# linearSensor.net
KiCad netlist of a schematic drawn in EAGLE
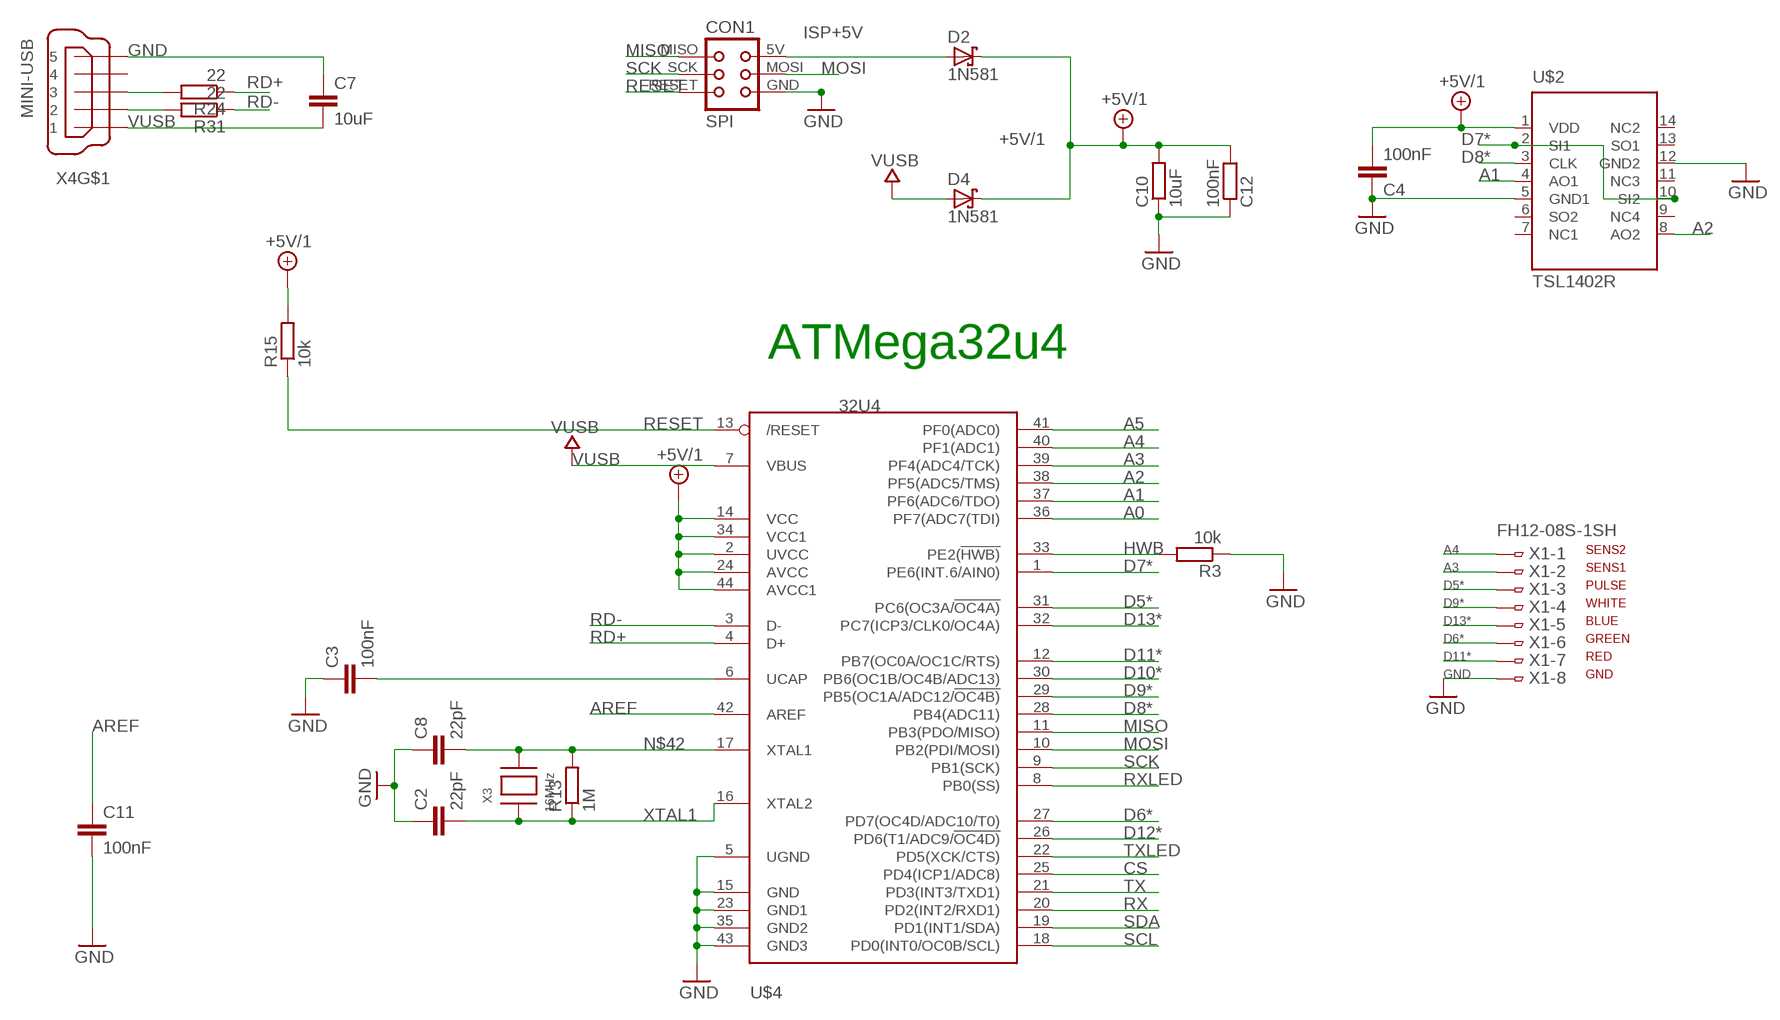
[diagram p0: schematic, sheet 1]

(export (version "E")
  (design (tool "Eeschema 10.0.6"))
  (components
    (comp (ref "C2")
      (value "22pF")
      (footprint "eagle-import:C0805K")
      (libsource (lib "eagle-import") (part "C-EUC0805K"))
    )
    (comp (ref "C3")
      (value "100nF")
      (footprint "eagle-import:C0805K")
      (libsource (lib "eagle-import") (part "C-EUC0805K"))
    )
    (comp (ref "C4")
      (value "100nF")
      (footprint "eagle-import:C0805")
      (libsource (lib "eagle-import") (part "C-EUC0805"))
    )
    (comp (ref "C7")
      (value "10uF")
      (footprint "eagle-import:C0805")
      (libsource (lib "eagle-import") (part "C-EUC0805"))
    )
    (comp (ref "C8")
      (value "22pF")
      (footprint "eagle-import:C0805K")
      (libsource (lib "eagle-import") (part "C-EUC0805K"))
    )
    (comp (ref "C10")
      (value "10uF")
      (footprint "eagle-import:M0805")
      (libsource (lib "eagle-import") (part "R-EU_M0805"))
    )
    (comp (ref "C11")
      (value "100nF")
      (footprint "eagle-import:C0805K")
      (libsource (lib "eagle-import") (part "C-EUC0805K"))
    )
    (comp (ref "C12")
      (value "100nF")
      (footprint "eagle-import:M0805")
      (libsource (lib "eagle-import") (part "R-EU_M0805"))
    )
    (comp (ref "CON1")
      (value "SPI")
      (footprint "eagle-import:TC2030-MCP-NL")
      (libsource (lib "eagle-import") (part "TINYISPT"))
    )
    (comp (ref "D2")
      (value "1N581")
      (footprint "eagle-import:LED-1206")
      (libsource (lib "eagle-import") (part "1N581D1206"))
    )
    (comp (ref "D4")
      (value "1N581")
      (footprint "eagle-import:LED-1206")
      (libsource (lib "eagle-import") (part "1N581D1206"))
    )
    (comp (ref "R3")
      (value "10k")
      (footprint "eagle-import:M0805")
      (libsource (lib "eagle-import") (part "resistor_R-EU_M0805"))
    )
    (comp (ref "R13")
      (value "1M")
      (footprint "eagle-import:M0805")
      (libsource (lib "eagle-import") (part "R-EU_M0805"))
    )
    (comp (ref "R15")
      (value "10k")
      (footprint "eagle-import:M0805")
      (libsource (lib "eagle-import") (part "resistor_R-EU_M0805"))
    )
    (comp (ref "R24")
      (value "22")
      (footprint "eagle-import:M0805")
      (libsource (lib "eagle-import") (part "R-EU_M0805"))
    )
    (comp (ref "R31")
      (value "22")
      (footprint "eagle-import:M0805")
      (libsource (lib "eagle-import") (part "R-EU_M0805"))
    )
    (comp (ref "U$2")
      (value "TSL1402R")
      (footprint "eagle-import:DIL14")
      (libsource (lib "eagle-import") (part "TSL1402R"))
    )
    (comp (ref "U$4")
      (value "32U4")
      (footprint "eagle-import:TQFP44")
      (libsource (lib "eagle-import") (part "ATMEGA32U4-AU"))
    )
    (comp (ref "X1")
      (value "FH12-08S-1SH")
      (footprint "eagle-import:FH12-08S-1SH")
      (libsource (lib "eagle-import") (part "FH12-08S-1SH"))
    )
    (comp (ref "X3")
      (value "16MHz")
      (footprint "eagle-import:NX6035")
      (libsource (lib "eagle-import") (part "XTALNX6035"))
    )
    (comp (ref "X4")
      (value "MINI-USB")
      (footprint "eagle-import:32005-201")
      (libsource (lib "eagle-import") (part "MINI-USB-SCHIELD-32005-201"))
    )
  )
  (nets
    (net (code "1") (name "+5V{slash}1") (class "Default")
      (node (ref "C10") (pin "2") (pinfunction "2_2") (pintype "passive"))
      (node (ref "C12") (pin "2") (pinfunction "2_2") (pintype "passive"))
      (node (ref "C4") (pin "2") (pinfunction "2_2") (pintype "passive"))
      (node (ref "D2") (pin "C") (pinfunction "C_C") (pintype "passive"))
      (node (ref "D4") (pin "C") (pinfunction "C_C") (pintype "passive"))
      (node (ref "R15") (pin "2") (pinfunction "2_2") (pintype "passive"))
      (node (ref "U$2") (pin "1") (pinfunction "VDD_1") (pintype "power_in"))
      (node (ref "U$4") (pin "14") (pinfunction "VCC_14") (pintype "bidirectional"))
      (node (ref "U$4") (pin "2") (pinfunction "UVCC_2") (pintype "bidirectional"))
      (node (ref "U$4") (pin "24") (pinfunction "AVCC_24") (pintype "bidirectional"))
      (node (ref "U$4") (pin "34") (pinfunction "VCC1_34") (pintype "bidirectional"))
      (node (ref "U$4") (pin "44") (pinfunction "AVCC1_44") (pintype "bidirectional"))
    )
    (net (code "2") (name "/A0") (class "Default")
      (node (ref "U$4") (pin "36") (pinfunction "PF7(ADC7(TDI)_36") (pintype "bidirectional"))
    )
    (net (code "3") (name "/A1") (class "Default")
      (node (ref "U$2") (pin "4") (pinfunction "AO1_4") (pintype "output"))
      (node (ref "U$4") (pin "37") (pinfunction "PF6(ADC6/TDO)_37") (pintype "bidirectional"))
    )
    (net (code "4") (name "/A2") (class "Default")
      (node (ref "U$2") (pin "8") (pinfunction "AO2_8") (pintype "output"))
      (node (ref "U$4") (pin "38") (pinfunction "PF5(ADC5/TMS)_38") (pintype "bidirectional"))
    )
    (net (code "5") (name "/A3") (class "Default")
      (node (ref "U$4") (pin "39") (pinfunction "PF4(ADC4/TCK)_39") (pintype "bidirectional"))
      (node (ref "X1") (pin "2") (pinfunction "1_2") (pintype "passive"))
    )
    (net (code "6") (name "/A4") (class "Default")
      (node (ref "U$4") (pin "40") (pinfunction "PF1(ADC1)_40") (pintype "bidirectional"))
      (node (ref "X1") (pin "1") (pinfunction "1_1") (pintype "passive"))
    )
    (net (code "7") (name "/A5") (class "Default")
      (node (ref "U$4") (pin "41") (pinfunction "PF0(ADC0)_41") (pintype "bidirectional"))
    )
    (net (code "8") (name "/AREF") (class "Default")
      (node (ref "C11") (pin "1") (pinfunction "1_1") (pintype "passive"))
      (node (ref "U$4") (pin "42") (pinfunction "AREF_42") (pintype "bidirectional"))
    )
    (net (code "9") (name "/CS") (class "Default")
      (node (ref "U$4") (pin "25") (pinfunction "PD4(ICP1/ADC8)_25") (pintype "bidirectional"))
    )
    (net (code "10") (name "/D5*") (class "Default")
      (node (ref "U$4") (pin "31") (pinfunction "PC6(OC3A/~{OC4A})_31") (pintype "bidirectional"))
      (node (ref "X1") (pin "3") (pinfunction "1_3") (pintype "passive"))
    )
    (net (code "11") (name "/D6*") (class "Default")
      (node (ref "U$4") (pin "27") (pinfunction "PD7(OC4D/ADC10/T0)_27") (pintype "bidirectional"))
      (node (ref "X1") (pin "6") (pinfunction "1_6") (pintype "passive"))
    )
    (net (code "12") (name "/D7*") (class "Default")
      (node (ref "U$2") (pin "10") (pinfunction "SI2_10") (pintype "input"))
      (node (ref "U$2") (pin "2") (pinfunction "SI1_2") (pintype "input"))
      (node (ref "U$4") (pin "1") (pinfunction "PE6(INT.6/AIN0)_1") (pintype "bidirectional"))
    )
    (net (code "13") (name "/D8*") (class "Default")
      (node (ref "U$2") (pin "3") (pinfunction "CLK_3") (pintype "input"))
      (node (ref "U$4") (pin "28") (pinfunction "PB4(ADC11)_28") (pintype "bidirectional"))
    )
    (net (code "14") (name "/D9*") (class "Default")
      (node (ref "U$4") (pin "29") (pinfunction "PB5(OC1A/ADC12/~{OC4B})_29") (pintype "bidirectional"))
      (node (ref "X1") (pin "4") (pinfunction "1_4") (pintype "passive"))
    )
    (net (code "15") (name "/D10*") (class "Default")
      (node (ref "U$4") (pin "30") (pinfunction "PB6(OC1B/OC4B/ADC13)_30") (pintype "bidirectional"))
    )
    (net (code "16") (name "/D11*") (class "Default")
      (node (ref "U$4") (pin "12") (pinfunction "PB7(OC0A/OC1C/RTS)_12") (pintype "bidirectional"))
      (node (ref "X1") (pin "7") (pinfunction "1_7") (pintype "passive"))
    )
    (net (code "17") (name "/D12*") (class "Default")
      (node (ref "U$4") (pin "26") (pinfunction "PD6(T1/ADC9/~{OC4D})_26") (pintype "bidirectional"))
    )
    (net (code "18") (name "/D13*") (class "Default")
      (node (ref "U$4") (pin "32") (pinfunction "PC7(ICP3/CLK0/OC4A)_32") (pintype "bidirectional"))
      (node (ref "X1") (pin "5") (pinfunction "1_5") (pintype "passive"))
    )
    (net (code "19") (name "/HWB") (class "Default")
      (node (ref "R3") (pin "2") (pinfunction "2_2") (pintype "passive"))
      (node (ref "U$4") (pin "33") (pinfunction "PE2(~{HWB})_33") (pintype "bidirectional"))
    )
    (net (code "20") (name "/ISP+5V") (class "Default")
      (node (ref "CON1") (pin "5V") (pinfunction "VCC_5V") (pintype "passive"))
      (node (ref "D2") (pin "A") (pinfunction "A_A") (pintype "passive"))
    )
    (net (code "21") (name "/MISO") (class "Default")
      (node (ref "CON1") (pin "MISO") (pinfunction "MISO_MISO") (pintype "passive"))
      (node (ref "U$4") (pin "11") (pinfunction "PB3(PDO/MISO)_11") (pintype "bidirectional"))
    )
    (net (code "22") (name "/MOSI") (class "Default")
      (node (ref "CON1") (pin "MOSI") (pinfunction "MOSI_MOSI") (pintype "passive"))
      (node (ref "U$4") (pin "10") (pinfunction "PB2(PDI/MOSI)_10") (pintype "bidirectional"))
    )
    (net (code "23") (name "/N$42") (class "Default")
      (node (ref "C8") (pin "2") (pinfunction "2_2") (pintype "passive"))
      (node (ref "R13") (pin "2") (pinfunction "2_2") (pintype "passive"))
      (node (ref "U$4") (pin "17") (pinfunction "XTAL1_17") (pintype "bidirectional"))
      (node (ref "X3") (pin "P$2") (pinfunction "P$2_P$2") (pintype "bidirectional"))
    )
    (net (code "24") (name "/RD+") (class "Default")
      (node (ref "R24") (pin "1") (pinfunction "1_1") (pintype "passive"))
      (node (ref "U$4") (pin "4") (pinfunction "D+_4") (pintype "bidirectional"))
    )
    (net (code "25") (name "/RD-") (class "Default")
      (node (ref "R31") (pin "1") (pinfunction "1_1") (pintype "passive"))
      (node (ref "U$4") (pin "3") (pinfunction "D-_3") (pintype "bidirectional"))
    )
    (net (code "26") (name "/RESET") (class "Default")
      (node (ref "CON1") (pin "RESET") (pinfunction "RESET_RESET") (pintype "passive"))
      (node (ref "R15") (pin "1") (pinfunction "1_1") (pintype "passive"))
      (node (ref "U$4") (pin "13") (pinfunction "/RESET_13") (pintype "bidirectional"))
    )
    (net (code "27") (name "/RX") (class "Default")
      (node (ref "U$4") (pin "20") (pinfunction "PD2(INT2/RXD1)_20") (pintype "bidirectional"))
    )
    (net (code "28") (name "/RXLED") (class "Default")
      (node (ref "U$4") (pin "8") (pinfunction "PB0(SS)_8") (pintype "bidirectional"))
    )
    (net (code "29") (name "/SCK") (class "Default")
      (node (ref "CON1") (pin "SCK") (pinfunction "SCK_SCK") (pintype "passive"))
      (node (ref "U$4") (pin "9") (pinfunction "PB1(SCK)_9") (pintype "bidirectional"))
    )
    (net (code "30") (name "/SCL") (class "Default")
      (node (ref "U$4") (pin "18") (pinfunction "PD0(INT0/OC0B/SCL)_18") (pintype "bidirectional"))
    )
    (net (code "31") (name "/SDA") (class "Default")
      (node (ref "U$4") (pin "19") (pinfunction "PD1(INT1/SDA)_19") (pintype "bidirectional"))
    )
    (net (code "32") (name "/TX") (class "Default")
      (node (ref "U$4") (pin "21") (pinfunction "PD3(INT3/TXD1)_21") (pintype "bidirectional"))
    )
    (net (code "33") (name "/TXLED") (class "Default")
      (node (ref "U$4") (pin "22") (pinfunction "PD5(XCK/CTS)_22") (pintype "bidirectional"))
    )
    (net (code "34") (name "/XTAL1") (class "Default")
      (node (ref "C2") (pin "2") (pinfunction "2_2") (pintype "passive"))
      (node (ref "R13") (pin "1") (pinfunction "1_1") (pintype "passive"))
      (node (ref "U$4") (pin "16") (pinfunction "XTAL2_16") (pintype "bidirectional"))
      (node (ref "X3") (pin "P$1") (pinfunction "P$1_P$1") (pintype "bidirectional"))
    )
    (net (code "35") (name "GND") (class "Default")
      (node (ref "C10") (pin "1") (pinfunction "1_1") (pintype "passive"))
      (node (ref "C11") (pin "2") (pinfunction "2_2") (pintype "passive"))
      (node (ref "C12") (pin "1") (pinfunction "1_1") (pintype "passive"))
      (node (ref "C2") (pin "1") (pinfunction "1_1") (pintype "passive"))
      (node (ref "C3") (pin "1") (pinfunction "1_1") (pintype "passive"))
      (node (ref "C4") (pin "1") (pinfunction "1_1") (pintype "passive"))
      (node (ref "C7") (pin "1") (pinfunction "1_1") (pintype "passive"))
      (node (ref "C8") (pin "1") (pinfunction "1_1") (pintype "passive"))
      (node (ref "CON1") (pin "GND") (pinfunction "GND_GND") (pintype "passive"))
      (node (ref "R3") (pin "1") (pinfunction "1_1") (pintype "passive"))
      (node (ref "U$2") (pin "12") (pinfunction "GND2_12") (pintype "power_in"))
      (node (ref "U$2") (pin "5") (pinfunction "GND1_5") (pintype "power_in"))
      (node (ref "U$4") (pin "15") (pinfunction "GND_15") (pintype "bidirectional"))
      (node (ref "U$4") (pin "23") (pinfunction "GND1_23") (pintype "bidirectional"))
      (node (ref "U$4") (pin "35") (pinfunction "GND2_35") (pintype "bidirectional"))
      (node (ref "U$4") (pin "43") (pinfunction "GND3_43") (pintype "bidirectional"))
      (node (ref "U$4") (pin "5") (pinfunction "UGND_5") (pintype "bidirectional"))
      (node (ref "X1") (pin "8") (pinfunction "1_8") (pintype "passive"))
      (node (ref "X4") (pin "5") (pinfunction "5_5") (pintype "passive"))
    )
    (net (code "36") (name "Net-(R24-Pad2)") (class "Default")
      (node (ref "R24") (pin "2") (pinfunction "2_2") (pintype "passive"))
      (node (ref "X4") (pin "3") (pinfunction "3_3") (pintype "passive"))
    )
    (net (code "37") (name "Net-(R31-Pad2)") (class "Default")
      (node (ref "R31") (pin "2") (pinfunction "2_2") (pintype "passive"))
      (node (ref "X4") (pin "2") (pinfunction "2_2") (pintype "passive"))
    )
    (net (code "38") (name "Net-(U$4-UCAP)") (class "Default")
      (node (ref "C3") (pin "2") (pinfunction "2_2") (pintype "passive"))
      (node (ref "U$4") (pin "6") (pinfunction "UCAP_6") (pintype "bidirectional"))
    )
    (net (code "39") (name "VUSB") (class "Default")
      (node (ref "C7") (pin "2") (pinfunction "2_2") (pintype "passive"))
      (node (ref "D4") (pin "A") (pinfunction "A_A") (pintype "passive"))
      (node (ref "U$4") (pin "7") (pinfunction "VBUS_7") (pintype "bidirectional"))
      (node (ref "X4") (pin "1") (pinfunction "1_1") (pintype "passive"))
    )
    (net (code "40") (name "unconnected-(U$2-NC1-Pad7)") (class "Default")
      (node (ref "U$2") (pin "7") (pinfunction "NC1_7") (pintype "no_connect"))
    )
    (net (code "41") (name "unconnected-(U$2-NC2-Pad14)") (class "Default")
      (node (ref "U$2") (pin "14") (pinfunction "NC2_14") (pintype "no_connect"))
    )
    (net (code "42") (name "unconnected-(U$2-NC3-Pad11)") (class "Default")
      (node (ref "U$2") (pin "11") (pinfunction "NC3_11") (pintype "no_connect"))
    )
    (net (code "43") (name "unconnected-(U$2-NC4-Pad9)") (class "Default")
      (node (ref "U$2") (pin "9") (pinfunction "NC4_9") (pintype "no_connect"))
    )
    (net (code "44") (name "unconnected-(U$2-SO1-Pad13)") (class "Default")
      (node (ref "U$2") (pin "13") (pinfunction "SO1_13") (pintype "output"))
    )
    (net (code "45") (name "unconnected-(U$2-SO2-Pad6)") (class "Default")
      (node (ref "U$2") (pin "6") (pinfunction "SO2_6") (pintype "output"))
    )
    (net (code "46") (name "unconnected-(X4-Pad4)") (class "Default")
      (node (ref "X4") (pin "4") (pinfunction "4_4") (pintype "passive"))
    )
  )
)
